# untitled.net
KiCad netlist of a schematic drawn in EAGLE
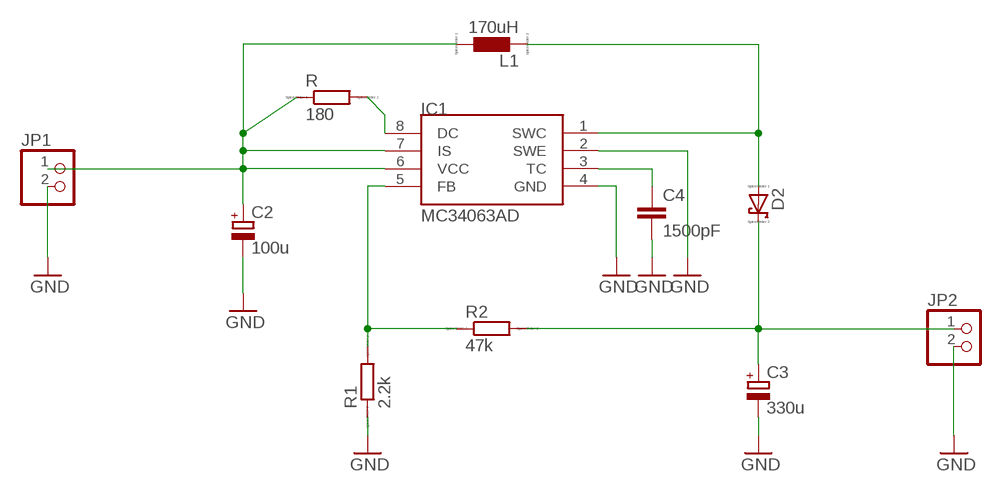
[diagram p0: schematic, sheet 1]

(export (version "E")
  (design (tool "Eeschema 10.0.6"))
  (components
    (comp (ref "C2")
      (value "100u")
      (footprint "eagle-import:E1,8-4")
      (libsource (lib "eagle-import") (part "CPOL-EUE1.8-4"))
    )
    (comp (ref "C3")
      (value "330u")
      (footprint "eagle-import:E1,8-4")
      (libsource (lib "eagle-import") (part "CPOL-EUE1.8-4"))
    )
    (comp (ref "C4")
      (value "1500pF")
      (footprint "eagle-import:C2.5-3")
      (libsource (lib "eagle-import") (part "C2,5-3"))
    )
    (comp (ref "D2")
      (value "SCHOTTKY-DIODEDO35-7")
      (footprint "eagle-import:DIODE_DO35-7")
      (libsource (lib "eagle-import") (part "SCHOTTKY-DIODEDO35-7"))
    )
    (comp (ref "IC1")
      (value "MC34063AD")
      (footprint "eagle-import:SOIC8")
      (libsource (lib "eagle-import") (part "MC34063AD"))
    )
    (comp (ref "JP1")
      (value "PINHD-1X2")
      (footprint "eagle-import:1X02")
      (libsource (lib "eagle-import") (part "PINHD-1X2"))
    )
    (comp (ref "JP2")
      (value "PINHD-1X2")
      (footprint "eagle-import:1X02")
      (libsource (lib "eagle-import") (part "PINHD-1X2"))
    )
    (comp (ref "L1")
      (value "170uH")
      (footprint "eagle-import:0204_7")
      (libsource (lib "eagle-import") (part "L0204/7"))
    )
    (comp (ref "R")
      (value "180")
      (footprint "eagle-import:0204_7")
      (libsource (lib "eagle-import") (part "R0204/7"))
    )
    (comp (ref "R1")
      (value "2.2k")
      (footprint "eagle-import:0204_7")
      (libsource (lib "eagle-import") (part "R0204/7"))
    )
    (comp (ref "R2")
      (value "47k")
      (footprint "eagle-import:0204_7")
      (libsource (lib "eagle-import") (part "R0204/7"))
    )
  )
  (nets
    (net (code "1") (name "GND") (class "Default")
      (node (ref "C2") (pin "-") (pinfunction "-_-") (pintype "passive"))
      (node (ref "C3") (pin "-") (pinfunction "-_-") (pintype "passive"))
      (node (ref "C4") (pin "2") (pinfunction "2_2") (pintype "passive"))
      (node (ref "IC1") (pin "2") (pinfunction "SWE_2") (pintype "passive"))
      (node (ref "IC1") (pin "4") (pinfunction "GND_4") (pintype "passive"))
      (node (ref "JP1") (pin "2") (pinfunction "2_2") (pintype "passive"))
      (node (ref "JP2") (pin "2") (pinfunction "2_2") (pintype "passive"))
      (node (ref "R1") (pin "1") (pinfunction "1_1") (pintype "passive"))
    )
    (net (code "2") (name "Net-(D2-A)") (class "Default")
      (node (ref "C3") (pin "+") (pinfunction "+_+") (pintype "passive"))
      (node (ref "D2") (pin "C") (pinfunction "A_C") (pintype "passive"))
      (node (ref "JP2") (pin "1") (pinfunction "1_1") (pintype "passive"))
      (node (ref "R2") (pin "2") (pinfunction "2_2") (pintype "passive"))
    )
    (net (code "3") (name "Net-(D2-C)") (class "Default")
      (node (ref "D2") (pin "A") (pinfunction "C_A") (pintype "passive"))
      (node (ref "IC1") (pin "1") (pinfunction "SWC_1") (pintype "passive"))
      (node (ref "L1") (pin "2") (pinfunction "2_2") (pintype "passive"))
    )
    (net (code "4") (name "Net-(IC1-DC)") (class "Default")
      (node (ref "IC1") (pin "8") (pinfunction "DC_8") (pintype "passive"))
      (node (ref "R") (pin "2") (pinfunction "2_2") (pintype "passive"))
    )
    (net (code "5") (name "Net-(IC1-FB)") (class "Default")
      (node (ref "IC1") (pin "5") (pinfunction "FB_5") (pintype "passive"))
      (node (ref "R1") (pin "2") (pinfunction "2_2") (pintype "passive"))
      (node (ref "R2") (pin "1") (pinfunction "1_1") (pintype "passive"))
    )
    (net (code "6") (name "Net-(IC1-IS)") (class "Default")
      (node (ref "C2") (pin "+") (pinfunction "+_+") (pintype "passive"))
      (node (ref "IC1") (pin "6") (pinfunction "VCC_6") (pintype "passive"))
      (node (ref "IC1") (pin "7") (pinfunction "IS_7") (pintype "passive"))
      (node (ref "JP1") (pin "1") (pinfunction "1_1") (pintype "passive"))
      (node (ref "L1") (pin "1") (pinfunction "1_1") (pintype "passive"))
      (node (ref "R") (pin "1") (pinfunction "1_1") (pintype "passive"))
    )
    (net (code "7") (name "Net-(IC1-TC)") (class "Default")
      (node (ref "C4") (pin "1") (pinfunction "1_1") (pintype "passive"))
      (node (ref "IC1") (pin "3") (pinfunction "TC_3") (pintype "passive"))
    )
  )
)
